# midicontrol_v6.net
KiCad netlist of a schematic drawn in EAGLE
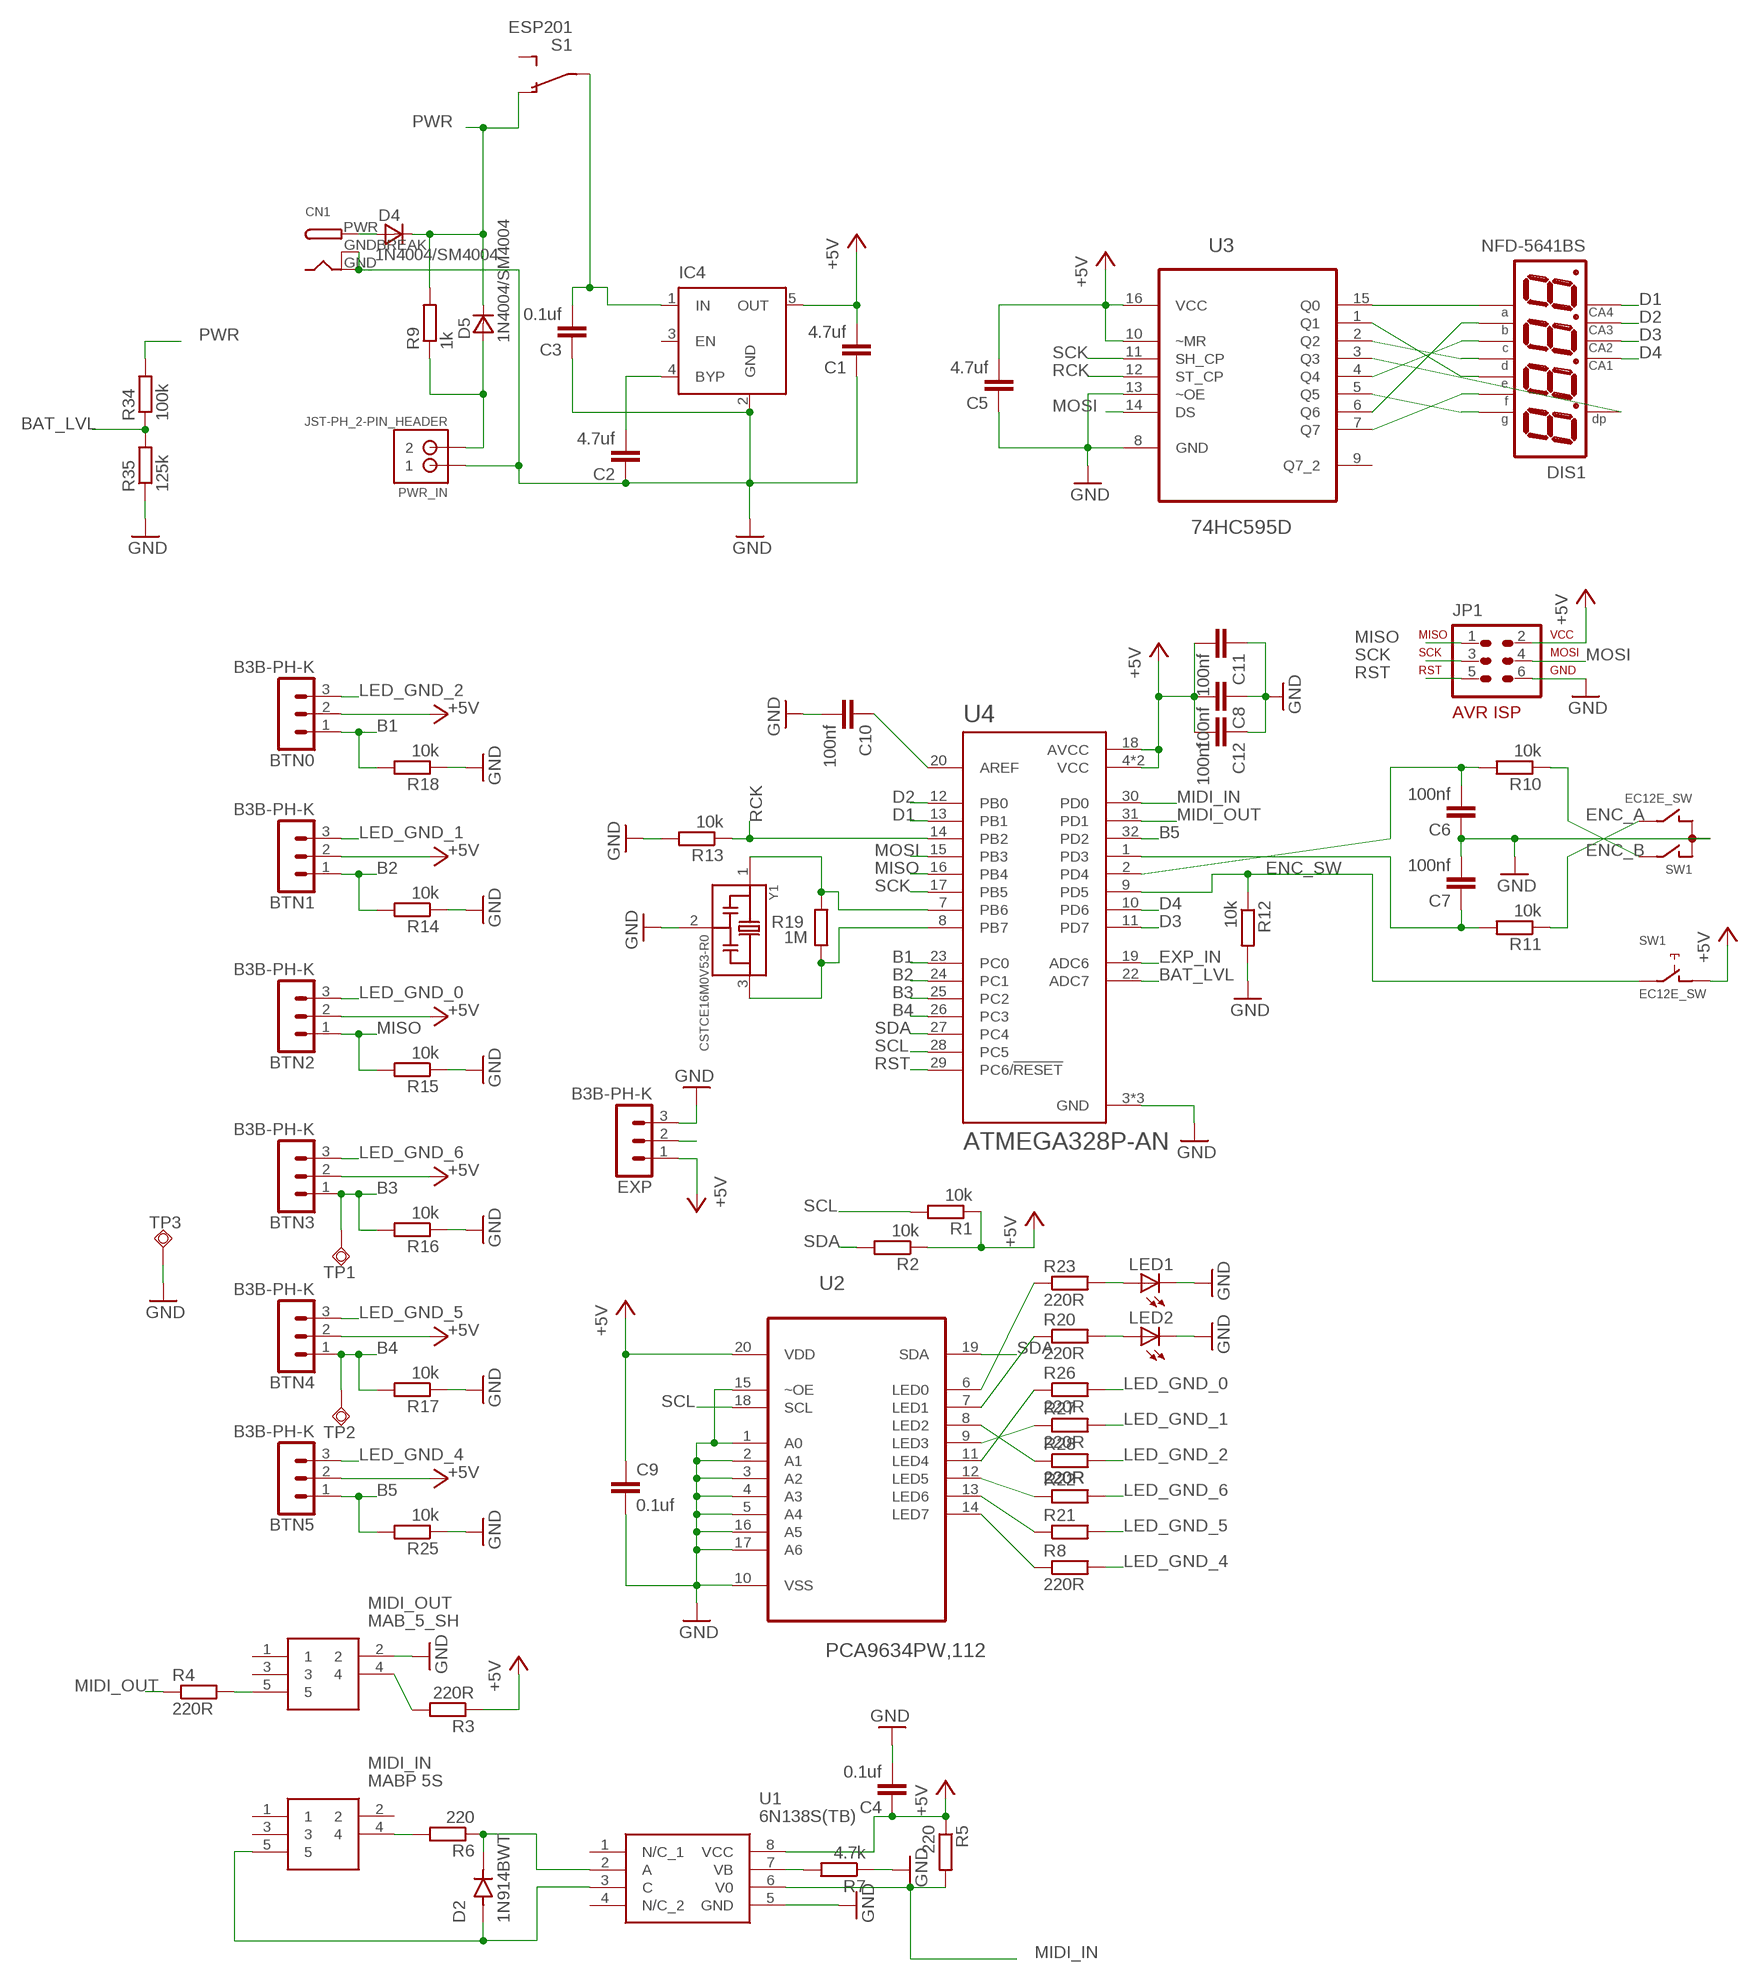
[diagram p0: schematic, sheet 1]

(export (version "E")
  (design (tool "Eeschema 10.0.6"))
  (components
    (comp (ref "BTN0")
      (value "B3B-PH-K")
      (footprint "eagle-import:B3B-PH-K")
      (libsource (lib "eagle-import") (part "B3B-PH-K"))
    )
    (comp (ref "BTN1")
      (value "B3B-PH-K")
      (footprint "eagle-import:B3B-PH-K")
      (libsource (lib "eagle-import") (part "B3B-PH-K"))
    )
    (comp (ref "BTN2")
      (value "B3B-PH-K")
      (footprint "eagle-import:B3B-PH-K")
      (libsource (lib "eagle-import") (part "B3B-PH-K"))
    )
    (comp (ref "BTN3")
      (value "B3B-PH-K")
      (footprint "eagle-import:B3B-PH-K")
      (libsource (lib "eagle-import") (part "B3B-PH-K"))
    )
    (comp (ref "BTN4")
      (value "B3B-PH-K")
      (footprint "eagle-import:B3B-PH-K")
      (libsource (lib "eagle-import") (part "B3B-PH-K"))
    )
    (comp (ref "BTN5")
      (value "B3B-PH-K")
      (footprint "eagle-import:B3B-PH-K")
      (libsource (lib "eagle-import") (part "B3B-PH-K"))
    )
    (comp (ref "C1")
      (value "4.7uf")
      (footprint "eagle-import:C1206")
      (libsource (lib "eagle-import") (part "C-EUC1206"))
    )
    (comp (ref "C2")
      (value "4.7uf")
      (footprint "eagle-import:C1206")
      (libsource (lib "eagle-import") (part "C-EUC1206"))
    )
    (comp (ref "C3")
      (value "0.1uf")
      (footprint "eagle-import:C0603")
      (libsource (lib "eagle-import") (part "C-EUC0603"))
    )
    (comp (ref "C4")
      (value "0.1uf")
      (footprint "eagle-import:C0603")
      (libsource (lib "eagle-import") (part "C-EUC0603"))
    )
    (comp (ref "C5")
      (value "4.7uf")
      (footprint "eagle-import:C0603")
      (libsource (lib "eagle-import") (part "C-EUC0603"))
    )
    (comp (ref "C6")
      (value "100nf")
      (footprint "eagle-import:C0603")
      (libsource (lib "eagle-import") (part "C-EUC0603"))
    )
    (comp (ref "C7")
      (value "100nf")
      (footprint "eagle-import:C0603")
      (libsource (lib "eagle-import") (part "C-EUC0603"))
    )
    (comp (ref "C8")
      (value "100nf")
      (footprint "eagle-import:C1206")
      (libsource (lib "eagle-import") (part "C-EUC1206"))
    )
    (comp (ref "C9")
      (value "0.1uf")
      (footprint "eagle-import:C0603")
      (libsource (lib "eagle-import") (part "C-EUC0603"))
    )
    (comp (ref "C10")
      (value "100nf")
      (footprint "eagle-import:C0603")
      (libsource (lib "eagle-import") (part "C-EUC0603"))
    )
    (comp (ref "C11")
      (value "100nf")
      (footprint "eagle-import:C0603")
      (libsource (lib "eagle-import") (part "C-EUC0603"))
    )
    (comp (ref "C12")
      (value "100nf")
      (footprint "eagle-import:C0603")
      (libsource (lib "eagle-import") (part "C-EUC0603"))
    )
    (comp (ref "CN1")
      (value "DCBARRELPTH")
      (footprint "eagle-import:DCJACK_2MM_PTH")
      (libsource (lib "eagle-import") (part "DCBARRELPTH"))
    )
    (comp (ref "D2")
      (value "1N914BWT")
      (footprint "eagle-import:SODFL1608X70N")
      (fields (field (name "MF") "ON Semiconductor"))
      (libsource (lib "eagle-import") (part "1N914BWT"))
    )
    (comp (ref "D4")
      (value "1N4004/SM4004")
      (footprint "eagle-import:MELF-MLL41")
      (libsource (lib "eagle-import") (part "SM4004"))
    )
    (comp (ref "D5")
      (value "1N4004/SM4004")
      (footprint "eagle-import:MELF-MLL41")
      (libsource (lib "eagle-import") (part "SM4004"))
    )
    (comp (ref "DIS1")
      (value "NFD-5641BS")
      (footprint "eagle-import:NFD-5641")
      (libsource (lib "eagle-import") (part "NFD-5641BS"))
    )
    (comp (ref "EXP")
      (value "B3B-PH-K")
      (footprint "eagle-import:B3B-PH-K")
      (libsource (lib "eagle-import") (part "B3B-PH-K"))
    )
    (comp (ref "IC4")
      (value "MIC5219XX")
      (footprint "eagle-import:SOT23-5")
      (libsource (lib "eagle-import") (part "MIC5219XX"))
    )
    (comp (ref "JP1")
      (value "AVR-ISP-6HORZ")
      (footprint "eagle-import:AVR-ISP-6R")
      (libsource (lib "eagle-import") (part "AVR-ISP-6HORZ"))
    )
    (comp (ref "LED1")
      (value "LED3MM")
      (footprint "eagle-import:LED3MM")
      (libsource (lib "eagle-import") (part "LED3MM"))
    )
    (comp (ref "LED2")
      (value "LED3MM")
      (footprint "eagle-import:LED3MM")
      (libsource (lib "eagle-import") (part "LED3MM"))
    )
    (comp (ref "MIDI_IN")
      (value "MABP 5S")
      (footprint "eagle-import:MAB-5-SH")
      (fields (field (name "MANUFACTURER_PART_NUMBER") "MAB 5 SH"))
      (libsource (lib "eagle-import") (part "MAB_5_SH"))
    )
    (comp (ref "MIDI_OUT")
      (value "MAB_5_SH")
      (footprint "eagle-import:MAB-5-SH")
      (fields (field (name "MANUFACTURER_PART_NUMBER") "MAB 5 SH"))
      (libsource (lib "eagle-import") (part "MAB_5_SH"))
    )
    (comp (ref "PWR_IN")
      (value "JST-PH_2-PIN_HEADER")
      (footprint "eagle-import:JST_B2B-PH_HEADER")
      (libsource (lib "eagle-import") (part "JST-PH_2-PIN_HEADER"))
    )
    (comp (ref "R1")
      (value "10k")
      (footprint "eagle-import:R0603")
      (libsource (lib "eagle-import") (part "rcl_334_R-EU_R0603"))
    )
    (comp (ref "R2")
      (value "10k")
      (footprint "eagle-import:R0603")
      (libsource (lib "eagle-import") (part "rcl_334_R-EU_R0603"))
    )
    (comp (ref "R3")
      (value "220R")
      (footprint "eagle-import:R0603")
      (libsource (lib "eagle-import") (part "rcl_334_R-EU_R0603"))
    )
    (comp (ref "R4")
      (value "220R")
      (footprint "eagle-import:R0603")
      (libsource (lib "eagle-import") (part "rcl_334_R-EU_R0603"))
    )
    (comp (ref "R5")
      (value "220")
      (footprint "eagle-import:R0603")
      (libsource (lib "eagle-import") (part "rcl_334_R-EU_R0603"))
    )
    (comp (ref "R6")
      (value "220")
      (footprint "eagle-import:R0603")
      (libsource (lib "eagle-import") (part "rcl_334_R-EU_R0603"))
    )
    (comp (ref "R7")
      (value "4.7k")
      (footprint "eagle-import:R0603")
      (libsource (lib "eagle-import") (part "rcl_334_R-EU_R0603"))
    )
    (comp (ref "R8")
      (value "220R")
      (footprint "eagle-import:R0603")
      (libsource (lib "eagle-import") (part "rcl_334_R-EU_R0603"))
    )
    (comp (ref "R9")
      (value "1k")
      (footprint "eagle-import:R0603")
      (libsource (lib "eagle-import") (part "rcl_334_R-EU_R0603"))
    )
    (comp (ref "R10")
      (value "10k")
      (footprint "eagle-import:R0603")
      (libsource (lib "eagle-import") (part "rcl_334_R-EU_R0603"))
    )
    (comp (ref "R11")
      (value "10k")
      (footprint "eagle-import:R0603")
      (libsource (lib "eagle-import") (part "rcl_334_R-EU_R0603"))
    )
    (comp (ref "R12")
      (value "10k")
      (footprint "eagle-import:R0603")
      (libsource (lib "eagle-import") (part "rcl_334_R-EU_R0603"))
    )
    (comp (ref "R13")
      (value "10k")
      (footprint "eagle-import:R0603")
      (libsource (lib "eagle-import") (part "rcl_334_R-EU_R0603"))
    )
    (comp (ref "R14")
      (value "10k")
      (footprint "eagle-import:R0603")
      (libsource (lib "eagle-import") (part "rcl_334_R-EU_R0603"))
    )
    (comp (ref "R15")
      (value "10k")
      (footprint "eagle-import:R0603")
      (libsource (lib "eagle-import") (part "rcl_334_R-EU_R0603"))
    )
    (comp (ref "R16")
      (value "10k")
      (footprint "eagle-import:R0603")
      (libsource (lib "eagle-import") (part "rcl_334_R-EU_R0603"))
    )
    (comp (ref "R17")
      (value "10k")
      (footprint "eagle-import:R0603")
      (libsource (lib "eagle-import") (part "rcl_334_R-EU_R0603"))
    )
    (comp (ref "R18")
      (value "10k")
      (footprint "eagle-import:R0603")
      (libsource (lib "eagle-import") (part "rcl_334_R-EU_R0603"))
    )
    (comp (ref "R19")
      (value "1M")
      (footprint "eagle-import:R0603-ROUND")
      (libsource (lib "eagle-import") (part "R-EU_R0603"))
    )
    (comp (ref "R20")
      (value "220R")
      (footprint "eagle-import:R0603")
      (libsource (lib "eagle-import") (part "rcl_334_R-EU_R0603"))
    )
    (comp (ref "R21")
      (value "220R")
      (footprint "eagle-import:R0603")
      (libsource (lib "eagle-import") (part "rcl_334_R-EU_R0603"))
    )
    (comp (ref "R22")
      (value "220R")
      (footprint "eagle-import:R0603")
      (libsource (lib "eagle-import") (part "rcl_334_R-EU_R0603"))
    )
    (comp (ref "R23")
      (value "220R")
      (footprint "eagle-import:R0603")
      (libsource (lib "eagle-import") (part "rcl_334_R-EU_R0603"))
    )
    (comp (ref "R25")
      (value "10k")
      (footprint "eagle-import:R0603")
      (libsource (lib "eagle-import") (part "rcl_334_R-EU_R0603"))
    )
    (comp (ref "R26")
      (value "220R")
      (footprint "eagle-import:R0603")
      (libsource (lib "eagle-import") (part "rcl_334_R-EU_R0603"))
    )
    (comp (ref "R27")
      (value "220R")
      (footprint "eagle-import:R0603")
      (libsource (lib "eagle-import") (part "rcl_334_R-EU_R0603"))
    )
    (comp (ref "R28")
      (value "220R")
      (footprint "eagle-import:R0603")
      (libsource (lib "eagle-import") (part "rcl_334_R-EU_R0603"))
    )
    (comp (ref "R34")
      (value "100k")
      (footprint "eagle-import:R0603")
      (libsource (lib "eagle-import") (part "rcl_334_R-EU_R0603"))
    )
    (comp (ref "R35")
      (value "125k")
      (footprint "eagle-import:R0603")
      (libsource (lib "eagle-import") (part "rcl_334_R-EU_R0603"))
    )
    (comp (ref "S1")
      (value "ESP201")
      (footprint "eagle-import:ESP201")
      (libsource (lib "eagle-import") (part "ESP201"))
    )
    (comp (ref "SW1")
      (value "EC12E_SW")
      (footprint "eagle-import:ALPS_EC12E_SW")
      (fields (field (name "MPN") "EC12E2424407"))
      (libsource (lib "eagle-import") (part "EC12E_SW"))
    )
    (comp (ref "TP1")
      (value "TPSQTP18R")
      (footprint "eagle-import:TP18R")
      (libsource (lib "eagle-import") (part "TPSQTP18R"))
    )
    (comp (ref "TP2")
      (value "TPSQTP18R")
      (footprint "eagle-import:TP18R")
      (libsource (lib "eagle-import") (part "TPSQTP18R"))
    )
    (comp (ref "TP3")
      (value "TPSQTP18R")
      (footprint "eagle-import:TP18R")
      (libsource (lib "eagle-import") (part "TPSQTP18R"))
    )
    (comp (ref "U1")
      (value "6N138S(TB)")
      (footprint "eagle-import:SOP254P1030X460-8N")
      (fields (field (name "MOUSER_PART_NUMBER") "638-6N138STB"))
      (libsource (lib "eagle-import") (part "6N138S(TB)"))
    )
    (comp (ref "U2")
      (value "PCA9634PW,112")
      (footprint "eagle-import:SOP65P640X110-20N")
      (fields (field (name "MF") "NXP USA"))
      (libsource (lib "eagle-import") (part "PCA9634PW,112"))
    )
    (comp (ref "U3")
      (value "74HC595D")
      (footprint "eagle-import:SOIC127P600X175-16N")
      (fields (field (name "MF") "Toshiba Semiconductor"))
      (libsource (lib "eagle-import") (part "74HC595D"))
    )
    (comp (ref "U4")
      (value "ATMEGA328P-AN")
      (footprint "eagle-import:QFP80P900X900X120-32N")
      (fields (field (name "MF") "Microchip"))
      (libsource (lib "eagle-import") (part "ATMEGA328P-AN"))
    )
    (comp (ref "Y1")
      (value "CSTCE16M0V53-R0")
      (footprint "eagle-import:OSC_CSTCE16M0V53-R0")
      (fields (field (name "MF") "Murata"))
      (libsource (lib "eagle-import") (part "CSTCE16M0V53-R0"))
    )
  )
  (nets
    (net (code "1") (name "+5V") (class "Default")
      (node (ref "BTN0") (pin "2") (pinfunction "2_2") (pintype "passive"))
      (node (ref "BTN1") (pin "2") (pinfunction "2_2") (pintype "passive"))
      (node (ref "BTN2") (pin "2") (pinfunction "2_2") (pintype "passive"))
      (node (ref "BTN3") (pin "2") (pinfunction "2_2") (pintype "passive"))
      (node (ref "BTN4") (pin "2") (pinfunction "2_2") (pintype "passive"))
      (node (ref "BTN5") (pin "2") (pinfunction "2_2") (pintype "passive"))
      (node (ref "C1") (pin "2") (pinfunction "2_2") (pintype "passive"))
      (node (ref "C11") (pin "2") (pinfunction "2_2") (pintype "passive"))
      (node (ref "C12") (pin "2") (pinfunction "2_2") (pintype "passive"))
      (node (ref "C4") (pin "1") (pinfunction "1_1") (pintype "passive"))
      (node (ref "C5") (pin "2") (pinfunction "2_2") (pintype "passive"))
      (node (ref "C8") (pin "2") (pinfunction "2_2") (pintype "passive"))
      (node (ref "C9") (pin "1") (pinfunction "1_1") (pintype "passive"))
      (node (ref "EXP") (pin "1") (pinfunction "1_1") (pintype "passive"))
      (node (ref "IC4") (pin "5") (pinfunction "OUT_5") (pintype "output"))
      (node (ref "JP1") (pin "2") (pinfunction "2_2") (pintype "passive"))
      (node (ref "R1") (pin "1") (pinfunction "1_1") (pintype "passive"))
      (node (ref "R2") (pin "1") (pinfunction "1_1") (pintype "passive"))
      (node (ref "R3") (pin "1") (pinfunction "1_1") (pintype "passive"))
      (node (ref "R5") (pin "1") (pinfunction "1_1") (pintype "passive"))
      (node (ref "SW1") (pin "D") (pinfunction "1_D") (pintype "passive"))
      (node (ref "U1") (pin "8") (pinfunction "VCC_8") (pintype "power_in"))
      (node (ref "U2") (pin "20") (pinfunction "VDD_20") (pintype "power_in"))
      (node (ref "U3") (pin "10") (pinfunction "~{MR}_10") (pintype "passive"))
      (node (ref "U3") (pin "16") (pinfunction "VCC_16") (pintype "power_in"))
      (node (ref "U4") (pin "18") (pinfunction "AVCC_18") (pintype "power_in"))
      (node (ref "U4") (pin "4") (pinfunction "VCC_4") (pintype "power_in"))
      (node (ref "U4") (pin "6") (pinfunction "VCC_6") (pintype "power_in"))
    )
    (net (code "2") (name "/B1") (class "Default")
      (node (ref "BTN0") (pin "1") (pinfunction "1_1") (pintype "passive"))
      (node (ref "R18") (pin "2") (pinfunction "2_2") (pintype "passive"))
      (node (ref "U4") (pin "23") (pinfunction "PC0_23") (pintype "bidirectional"))
    )
    (net (code "3") (name "/B2") (class "Default")
      (node (ref "BTN1") (pin "1") (pinfunction "1_1") (pintype "passive"))
      (node (ref "R14") (pin "2") (pinfunction "2_2") (pintype "passive"))
      (node (ref "U4") (pin "24") (pinfunction "PC1_24") (pintype "bidirectional"))
    )
    (net (code "4") (name "/B3") (class "Default")
      (node (ref "BTN3") (pin "1") (pinfunction "1_1") (pintype "passive"))
      (node (ref "R16") (pin "2") (pinfunction "2_2") (pintype "passive"))
      (node (ref "TP1") (pin "TP") (pinfunction "TP_TP") (pintype "input"))
      (node (ref "U4") (pin "25") (pinfunction "PC2_25") (pintype "bidirectional"))
    )
    (net (code "5") (name "/B4") (class "Default")
      (node (ref "BTN4") (pin "1") (pinfunction "1_1") (pintype "passive"))
      (node (ref "R17") (pin "2") (pinfunction "2_2") (pintype "passive"))
      (node (ref "TP2") (pin "TP") (pinfunction "TP_TP") (pintype "input"))
      (node (ref "U4") (pin "26") (pinfunction "PC3_26") (pintype "bidirectional"))
    )
    (net (code "6") (name "/B5") (class "Default")
      (node (ref "BTN5") (pin "1") (pinfunction "1_1") (pintype "passive"))
      (node (ref "R25") (pin "2") (pinfunction "2_2") (pintype "passive"))
      (node (ref "U4") (pin "32") (pinfunction "PD2_32") (pintype "bidirectional"))
    )
    (net (code "7") (name "/BAT_LVL") (class "Default")
      (node (ref "R34") (pin "1") (pinfunction "1_1") (pintype "passive"))
      (node (ref "R35") (pin "2") (pinfunction "2_2") (pintype "passive"))
      (node (ref "U4") (pin "22") (pinfunction "ADC7_22") (pintype "bidirectional"))
    )
    (net (code "8") (name "/D1") (class "Default")
      (node (ref "DIS1") (pin "P$6") (pinfunction "P$6_P$6") (pintype "bidirectional"))
      (node (ref "U4") (pin "13") (pinfunction "PB1_13") (pintype "bidirectional"))
    )
    (net (code "9") (name "/D2") (class "Default")
      (node (ref "DIS1") (pin "P$8") (pinfunction "P$8_P$8") (pintype "bidirectional"))
      (node (ref "U4") (pin "12") (pinfunction "PB0_12") (pintype "bidirectional"))
    )
    (net (code "10") (name "/D3") (class "Default")
      (node (ref "DIS1") (pin "P$9") (pinfunction "P$9_P$9") (pintype "bidirectional"))
      (node (ref "U4") (pin "11") (pinfunction "PD7_11") (pintype "bidirectional"))
    )
    (net (code "11") (name "/D4") (class "Default")
      (node (ref "DIS1") (pin "P$12") (pinfunction "P$12_P$12") (pintype "bidirectional"))
      (node (ref "U4") (pin "10") (pinfunction "PD6_10") (pintype "bidirectional"))
    )
    (net (code "12") (name "/ENC_A") (class "Default")
      (node (ref "R10") (pin "1") (pinfunction "1_1") (pintype "passive"))
      (node (ref "SW1") (pin "A") (pinfunction "A_A") (pintype "passive"))
    )
    (net (code "13") (name "/ENC_B") (class "Default")
      (node (ref "R11") (pin "1") (pinfunction "1_1") (pintype "passive"))
      (node (ref "SW1") (pin "B") (pinfunction "B_B") (pintype "passive"))
    )
    (net (code "14") (name "/ENC_SW") (class "Default")
      (node (ref "R12") (pin "1") (pinfunction "1_1") (pintype "passive"))
      (node (ref "SW1") (pin "E") (pinfunction "2_E") (pintype "passive"))
      (node (ref "U4") (pin "9") (pinfunction "PD5_9") (pintype "bidirectional"))
    )
    (net (code "15") (name "/EXP_IN") (class "Default")
      (node (ref "EXP") (pin "2") (pinfunction "2_2") (pintype "passive"))
      (node (ref "U4") (pin "19") (pinfunction "ADC6_19") (pintype "bidirectional"))
    )
    (net (code "16") (name "/LED_GND_0") (class "Default")
      (node (ref "BTN2") (pin "3") (pinfunction "3_3") (pintype "passive"))
      (node (ref "R26") (pin "2") (pinfunction "2_2") (pintype "passive"))
    )
    (net (code "17") (name "/LED_GND_1") (class "Default")
      (node (ref "BTN1") (pin "3") (pinfunction "3_3") (pintype "passive"))
      (node (ref "R27") (pin "2") (pinfunction "2_2") (pintype "passive"))
    )
    (net (code "18") (name "/LED_GND_2") (class "Default")
      (node (ref "BTN0") (pin "3") (pinfunction "3_3") (pintype "passive"))
      (node (ref "R28") (pin "2") (pinfunction "2_2") (pintype "passive"))
    )
    (net (code "19") (name "/LED_GND_4") (class "Default")
      (node (ref "BTN5") (pin "3") (pinfunction "3_3") (pintype "passive"))
      (node (ref "R8") (pin "2") (pinfunction "2_2") (pintype "passive"))
    )
    (net (code "20") (name "/LED_GND_5") (class "Default")
      (node (ref "BTN4") (pin "3") (pinfunction "3_3") (pintype "passive"))
      (node (ref "R21") (pin "2") (pinfunction "2_2") (pintype "passive"))
    )
    (net (code "21") (name "/LED_GND_6") (class "Default")
      (node (ref "BTN3") (pin "3") (pinfunction "3_3") (pintype "passive"))
      (node (ref "R22") (pin "2") (pinfunction "2_2") (pintype "passive"))
    )
    (net (code "22") (name "/MIDI_IN") (class "Default")
      (node (ref "R5") (pin "2") (pinfunction "2_2") (pintype "passive"))
      (node (ref "U1") (pin "6") (pinfunction "V0_6") (pintype "bidirectional"))
      (node (ref "U4") (pin "30") (pinfunction "PD0_30") (pintype "bidirectional"))
    )
    (net (code "23") (name "/MIDI_OUT") (class "Default")
      (node (ref "R4") (pin "1") (pinfunction "1_1") (pintype "passive"))
      (node (ref "U4") (pin "31") (pinfunction "PD1_31") (pintype "bidirectional"))
    )
    (net (code "24") (name "/MISO") (class "Default")
      (node (ref "BTN2") (pin "1") (pinfunction "1_1") (pintype "passive"))
      (node (ref "JP1") (pin "1") (pinfunction "1_1") (pintype "passive"))
      (node (ref "R15") (pin "2") (pinfunction "2_2") (pintype "passive"))
      (node (ref "U4") (pin "16") (pinfunction "PB4_16") (pintype "bidirectional"))
    )
    (net (code "25") (name "/MOSI") (class "Default")
      (node (ref "JP1") (pin "4") (pinfunction "4_4") (pintype "passive"))
      (node (ref "U3") (pin "14") (pinfunction "DS_14") (pintype "input"))
      (node (ref "U4") (pin "15") (pinfunction "PB3_15") (pintype "bidirectional"))
    )
    (net (code "26") (name "/PWR") (class "Default")
      (node (ref "D4") (pin "C") (pinfunction "C_C") (pintype "passive"))
      (node (ref "D5") (pin "C") (pinfunction "C_C") (pintype "passive"))
      (node (ref "R34") (pin "2") (pinfunction "2_2") (pintype "passive"))
      (node (ref "R9") (pin "2") (pinfunction "2_2") (pintype "passive"))
      (node (ref "S1") (pin "P$3") (pinfunction "O_P$3") (pintype "passive"))
    )
    (net (code "27") (name "/RCK") (class "Default")
      (node (ref "R13") (pin "1") (pinfunction "1_1") (pintype "passive"))
      (node (ref "U3") (pin "12") (pinfunction "ST_CP_12") (pintype "passive"))
      (node (ref "U4") (pin "14") (pinfunction "PB2_14") (pintype "bidirectional"))
    )
    (net (code "28") (name "/RST") (class "Default")
      (node (ref "JP1") (pin "5") (pinfunction "5_5") (pintype "passive"))
      (node (ref "U4") (pin "29") (pinfunction "PC6/~{RESET}_29") (pintype "bidirectional"))
    )
    (net (code "29") (name "/SCK") (class "Default")
      (node (ref "JP1") (pin "3") (pinfunction "3_3") (pintype "passive"))
      (node (ref "U3") (pin "11") (pinfunction "SH_CP_11") (pintype "passive"))
      (node (ref "U4") (pin "17") (pinfunction "PB5_17") (pintype "bidirectional"))
    )
    (net (code "30") (name "/SCL") (class "Default")
      (node (ref "R1") (pin "2") (pinfunction "2_2") (pintype "passive"))
      (node (ref "U2") (pin "18") (pinfunction "SCL_18") (pintype "input"))
      (node (ref "U4") (pin "28") (pinfunction "PC5_28") (pintype "bidirectional"))
    )
    (net (code "31") (name "/SDA") (class "Default")
      (node (ref "R2") (pin "2") (pinfunction "2_2") (pintype "passive"))
      (node (ref "U2") (pin "19") (pinfunction "SDA_19") (pintype "bidirectional"))
      (node (ref "U4") (pin "27") (pinfunction "PC4_27") (pintype "bidirectional"))
    )
    (net (code "32") (name "GND") (class "Default")
      (node (ref "C1") (pin "1") (pinfunction "1_1") (pintype "passive"))
      (node (ref "C10") (pin "2") (pinfunction "2_2") (pintype "passive"))
      (node (ref "C11") (pin "1") (pinfunction "1_1") (pintype "passive"))
      (node (ref "C12") (pin "1") (pinfunction "1_1") (pintype "passive"))
      (node (ref "C2") (pin "1") (pinfunction "1_1") (pintype "passive"))
      (node (ref "C3") (pin "1") (pinfunction "1_1") (pintype "passive"))
      (node (ref "C4") (pin "2") (pinfunction "2_2") (pintype "passive"))
      (node (ref "C5") (pin "1") (pinfunction "1_1") (pintype "passive"))
      (node (ref "C6") (pin "1") (pinfunction "1_1") (pintype "passive"))
      (node (ref "C7") (pin "2") (pinfunction "2_2") (pintype "passive"))
      (node (ref "C8") (pin "1") (pinfunction "1_1") (pintype "passive"))
      (node (ref "C9") (pin "2") (pinfunction "2_2") (pintype "passive"))
      (node (ref "CN1") (pin "GND") (pinfunction "GND_GND") (pintype "power_in"))
      (node (ref "CN1") (pin "GNDBREAK") (pinfunction "GNDBREAK_GNDBREAK") (pintype "power_in"))
      (node (ref "EXP") (pin "3") (pinfunction "3_3") (pintype "passive"))
      (node (ref "IC4") (pin "2") (pinfunction "GND_2") (pintype "power_in"))
      (node (ref "JP1") (pin "6") (pinfunction "6_6") (pintype "passive"))
      (node (ref "LED1") (pin "K") (pinfunction "C_K") (pintype "passive"))
      (node (ref "LED2") (pin "K") (pinfunction "C_K") (pintype "passive"))
      (node (ref "MIDI_OUT") (pin "2") (pinfunction "2_2") (pintype "bidirectional"))
      (node (ref "PWR_IN") (pin "P1") (pinfunction "1_P1") (pintype "bidirectional"))
      (node (ref "R12") (pin "2") (pinfunction "2_2") (pintype "passive"))
      (node (ref "R13") (pin "2") (pinfunction "2_2") (pintype "passive"))
      (node (ref "R14") (pin "1") (pinfunction "1_1") (pintype "passive"))
      (node (ref "R15") (pin "1") (pinfunction "1_1") (pintype "passive"))
      (node (ref "R16") (pin "1") (pinfunction "1_1") (pintype "passive"))
      (node (ref "R17") (pin "1") (pinfunction "1_1") (pintype "passive"))
      (node (ref "R18") (pin "1") (pinfunction "1_1") (pintype "passive"))
      (node (ref "R25") (pin "1") (pinfunction "1_1") (pintype "passive"))
      (node (ref "R35") (pin "1") (pinfunction "1_1") (pintype "passive"))
      (node (ref "R7") (pin "1") (pinfunction "1_1") (pintype "passive"))
      (node (ref "SW1") (pin "C") (pinfunction "C_C") (pintype "passive"))
      (node (ref "TP3") (pin "TP") (pinfunction "TP_TP") (pintype "input"))
      (node (ref "U1") (pin "5") (pinfunction "GND_5") (pintype "power_in"))
      (node (ref "U2") (pin "1") (pinfunction "A0_1") (pintype "input"))
      (node (ref "U2") (pin "10") (pinfunction "VSS_10") (pintype "power_in"))
      (node (ref "U2") (pin "15") (pinfunction "~{OE}_15") (pintype "input"))
      (node (ref "U2") (pin "16") (pinfunction "A5_16") (pintype "input"))
      (node (ref "U2") (pin "17") (pinfunction "A6_17") (pintype "input"))
      (node (ref "U2") (pin "2") (pinfunction "A1_2") (pintype "input"))
      (node (ref "U2") (pin "3") (pinfunction "A2_3") (pintype "input"))
      (node (ref "U2") (pin "4") (pinfunction "A3_4") (pintype "input"))
      (node (ref "U2") (pin "5") (pinfunction "A4_5") (pintype "input"))
      (node (ref "U3") (pin "13") (pinfunction "~{OE}_13") (pintype "input"))
      (node (ref "U3") (pin "8") (pinfunction "GND_8") (pintype "passive"))
      (node (ref "U4") (pin "21") (pinfunction "GND_21") (pintype "power_in"))
      (node (ref "U4") (pin "3") (pinfunction "GND_3") (pintype "power_in"))
      (node (ref "U4") (pin "5") (pinfunction "GND_5") (pintype "power_in"))
      (node (ref "Y1") (pin "2") (pinfunction "2_2") (pintype "power_in"))
    )
    (net (code "33") (name "Net-(CN1-PadPWR)") (class "Default")
      (node (ref "CN1") (pin "PWR") (pinfunction "PWR_PWR") (pintype "power_in"))
      (node (ref "D4") (pin "A") (pinfunction "A_A") (pintype "passive"))
    )
    (net (code "34") (name "Net-(D2-K)") (class "Default")
      (node (ref "D2") (pin "C") (pinfunction "K_C") (pintype "passive"))
      (node (ref "R6") (pin "1") (pinfunction "1_1") (pintype "passive"))
      (node (ref "U1") (pin "2") (pinfunction "A_2") (pintype "bidirectional"))
    )
    (net (code "35") (name "Net-(IC4-BYP)") (class "Default")
      (node (ref "C2") (pin "2") (pinfunction "2_2") (pintype "passive"))
      (node (ref "IC4") (pin "4") (pinfunction "BYP_4") (pintype "passive"))
    )
    (net (code "36") (name "Net-(IC4-IN)") (class "Default")
      (node (ref "C3") (pin "2") (pinfunction "2_2") (pintype "passive"))
      (node (ref "IC4") (pin "1") (pinfunction "IN_1") (pintype "input"))
      (node (ref "S1") (pin "P$1") (pinfunction "P_P$1") (pintype "passive"))
    )
    (net (code "37") (name "Net-(LED1-PadA)") (class "Default")
      (node (ref "LED1") (pin "A") (pinfunction "A_A") (pintype "passive"))
      (node (ref "R23") (pin "2") (pinfunction "2_2") (pintype "passive"))
    )
    (net (code "38") (name "Net-(LED2-PadA)") (class "Default")
      (node (ref "LED2") (pin "A") (pinfunction "A_A") (pintype "passive"))
      (node (ref "R20") (pin "2") (pinfunction "2_2") (pintype "passive"))
    )
    (net (code "39") (name "Net-(MIDI_IN-Pad4)") (class "Default")
      (node (ref "MIDI_IN") (pin "4") (pinfunction "4_4") (pintype "bidirectional"))
      (node (ref "R6") (pin "2") (pinfunction "2_2") (pintype "passive"))
    )
    (net (code "40") (name "Net-(MIDI_OUT-Pad4)") (class "Default")
      (node (ref "MIDI_OUT") (pin "4") (pinfunction "4_4") (pintype "bidirectional"))
      (node (ref "R3") (pin "2") (pinfunction "2_2") (pintype "passive"))
    )
    (net (code "41") (name "Net-(MIDI_OUT-Pad5)") (class "Default")
      (node (ref "MIDI_OUT") (pin "5") (pinfunction "5_5") (pintype "bidirectional"))
      (node (ref "R4") (pin "2") (pinfunction "2_2") (pintype "passive"))
    )
    (net (code "42") (name "Net-(PWR_IN-2)") (class "Default")
      (node (ref "D5") (pin "A") (pinfunction "A_A") (pintype "passive"))
      (node (ref "PWR_IN") (pin "P2") (pinfunction "2_P2") (pintype "bidirectional"))
      (node (ref "R9") (pin "1") (pinfunction "1_1") (pintype "passive"))
    )
    (net (code "43") (name "Net-(U1-C)") (class "Default")
      (node (ref "D2") (pin "A") (pinfunction "A_A") (pintype "passive"))
      (node (ref "MIDI_IN") (pin "5") (pinfunction "5_5") (pintype "bidirectional"))
      (node (ref "U1") (pin "3") (pinfunction "C_3") (pintype "bidirectional"))
    )
    (net (code "44") (name "Net-(U1-VB)") (class "Default")
      (node (ref "R7") (pin "2") (pinfunction "2_2") (pintype "passive"))
      (node (ref "U1") (pin "7") (pinfunction "VB_7") (pintype "bidirectional"))
    )
    (net (code "45") (name "Net-(U2-LED0)") (class "Default")
      (node (ref "R23") (pin "1") (pinfunction "1_1") (pintype "passive"))
      (node (ref "U2") (pin "6") (pinfunction "LED0_6") (pintype "output"))
    )
    (net (code "46") (name "Net-(U2-LED1)") (class "Default")
      (node (ref "R20") (pin "1") (pinfunction "1_1") (pintype "passive"))
      (node (ref "U2") (pin "7") (pinfunction "LED1_7") (pintype "output"))
    )
    (net (code "47") (name "Net-(U2-LED2)") (class "Default")
      (node (ref "R28") (pin "1") (pinfunction "1_1") (pintype "passive"))
      (node (ref "U2") (pin "8") (pinfunction "LED2_8") (pintype "output"))
    )
    (net (code "48") (name "Net-(U2-LED3)") (class "Default")
      (node (ref "R27") (pin "1") (pinfunction "1_1") (pintype "passive"))
      (node (ref "U2") (pin "9") (pinfunction "LED3_9") (pintype "output"))
    )
    (net (code "49") (name "Net-(U2-LED4)") (class "Default")
      (node (ref "R26") (pin "1") (pinfunction "1_1") (pintype "passive"))
      (node (ref "U2") (pin "11") (pinfunction "LED4_11") (pintype "output"))
    )
    (net (code "50") (name "Net-(U2-LED5)") (class "Default")
      (node (ref "R22") (pin "1") (pinfunction "1_1") (pintype "passive"))
      (node (ref "U2") (pin "12") (pinfunction "LED5_12") (pintype "output"))
    )
    (net (code "51") (name "Net-(U2-LED6)") (class "Default")
      (node (ref "R21") (pin "1") (pinfunction "1_1") (pintype "passive"))
      (node (ref "U2") (pin "13") (pinfunction "LED6_13") (pintype "output"))
    )
    (net (code "52") (name "Net-(U2-LED7)") (class "Default")
      (node (ref "R8") (pin "1") (pinfunction "1_1") (pintype "passive"))
      (node (ref "U2") (pin "14") (pinfunction "LED7_14") (pintype "output"))
    )
    (net (code "53") (name "Net-(U3-Q0)") (class "Default")
      (node (ref "DIS1") (pin "P$11") (pinfunction "P$11_P$11") (pintype "bidirectional"))
      (node (ref "U3") (pin "15") (pinfunction "Q0_15") (pintype "output"))
    )
    (net (code "54") (name "Net-(U3-Q1)") (class "Default")
      (node (ref "DIS1") (pin "P$1") (pinfunction "P$1_P$1") (pintype "bidirectional"))
      (node (ref "U3") (pin "1") (pinfunction "Q1_1") (pintype "output"))
    )
    (net (code "55") (name "Net-(U3-Q2)") (class "Default")
      (node (ref "DIS1") (pin "P$2") (pinfunction "P$2_P$2") (pintype "bidirectional"))
      (node (ref "U3") (pin "2") (pinfunction "Q2_2") (pintype "output"))
    )
    (net (code "56") (name "Net-(U3-Q3)") (class "Default")
      (node (ref "DIS1") (pin "P$3") (pinfunction "P$3_P$3") (pintype "bidirectional"))
      (node (ref "U3") (pin "3") (pinfunction "Q3_3") (pintype "output"))
    )
    (net (code "57") (name "Net-(U3-Q4)") (class "Default")
      (node (ref "DIS1") (pin "P$4") (pinfunction "P$4_P$4") (pintype "bidirectional"))
      (node (ref "U3") (pin "4") (pinfunction "Q4_4") (pintype "output"))
    )
    (net (code "58") (name "Net-(U3-Q5)") (class "Default")
      (node (ref "DIS1") (pin "P$5") (pinfunction "P$5_P$5") (pintype "bidirectional"))
      (node (ref "U3") (pin "5") (pinfunction "Q5_5") (pintype "output"))
    )
    (net (code "59") (name "Net-(U3-Q6)") (class "Default")
      (node (ref "DIS1") (pin "P$7") (pinfunction "P$7_P$7") (pintype "bidirectional"))
      (node (ref "U3") (pin "6") (pinfunction "Q6_6") (pintype "output"))
    )
    (net (code "60") (name "Net-(U3-Q7)") (class "Default")
      (node (ref "DIS1") (pin "P$10") (pinfunction "P$10_P$10") (pintype "bidirectional"))
      (node (ref "U3") (pin "7") (pinfunction "Q7_7") (pintype "output"))
    )
    (net (code "61") (name "Net-(U4-AREF)") (class "Default")
      (node (ref "C10") (pin "1") (pinfunction "1_1") (pintype "passive"))
      (node (ref "U4") (pin "20") (pinfunction "AREF_20") (pintype "input"))
    )
    (net (code "62") (name "Net-(U4-PB6)") (class "Default")
      (node (ref "R19") (pin "2") (pinfunction "2_2") (pintype "passive"))
      (node (ref "U4") (pin "7") (pinfunction "PB6_7") (pintype "bidirectional"))
      (node (ref "Y1") (pin "1") (pinfunction "1_1") (pintype "passive"))
    )
    (net (code "63") (name "Net-(U4-PB7)") (class "Default")
      (node (ref "R19") (pin "1") (pinfunction "1_1") (pintype "passive"))
      (node (ref "U4") (pin "8") (pinfunction "PB7_8") (pintype "bidirectional"))
      (node (ref "Y1") (pin "3") (pinfunction "3_3") (pintype "passive"))
    )
    (net (code "64") (name "Net-(U4-PD3)") (class "Default")
      (node (ref "C7") (pin "1") (pinfunction "1_1") (pintype "passive"))
      (node (ref "R11") (pin "2") (pinfunction "2_2") (pintype "passive"))
      (node (ref "U4") (pin "1") (pinfunction "PD3_1") (pintype "bidirectional"))
    )
    (net (code "65") (name "Net-(U4-PD4)") (class "Default")
      (node (ref "C6") (pin "2") (pinfunction "2_2") (pintype "passive"))
      (node (ref "R10") (pin "2") (pinfunction "2_2") (pintype "passive"))
      (node (ref "U4") (pin "2") (pinfunction "PD4_2") (pintype "bidirectional"))
    )
    (net (code "66") (name "unconnected-(IC4-EN-Pad3)") (class "Default")
      (node (ref "IC4") (pin "3") (pinfunction "EN_3") (pintype "input"))
    )
    (net (code "67") (name "unconnected-(MIDI_IN-Pad1)") (class "Default")
      (node (ref "MIDI_IN") (pin "1") (pinfunction "1_1") (pintype "bidirectional"))
    )
    (net (code "68") (name "unconnected-(MIDI_IN-Pad2)") (class "Default")
      (node (ref "MIDI_IN") (pin "2") (pinfunction "2_2") (pintype "bidirectional"))
    )
    (net (code "69") (name "unconnected-(MIDI_IN-Pad3)") (class "Default")
      (node (ref "MIDI_IN") (pin "3") (pinfunction "3_3") (pintype "bidirectional"))
    )
    (net (code "70") (name "unconnected-(MIDI_OUT-Pad1)") (class "Default")
      (node (ref "MIDI_OUT") (pin "1") (pinfunction "1_1") (pintype "bidirectional"))
    )
    (net (code "71") (name "unconnected-(MIDI_OUT-Pad3)") (class "Default")
      (node (ref "MIDI_OUT") (pin "3") (pinfunction "3_3") (pintype "bidirectional"))
    )
    (net (code "72") (name "unconnected-(S1-S-PadP$2)") (class "Default")
      (node (ref "S1") (pin "P$2") (pinfunction "S_P$2") (pintype "passive"))
    )
    (net (code "73") (name "unconnected-(U1-N{slash}C_1-Pad1)") (class "Default")
      (node (ref "U1") (pin "1") (pinfunction "N/C_1_1") (pintype "bidirectional"))
    )
    (net (code "74") (name "unconnected-(U1-N{slash}C_2-Pad4)") (class "Default")
      (node (ref "U1") (pin "4") (pinfunction "N/C_2_4") (pintype "bidirectional"))
    )
    (net (code "75") (name "unconnected-(U3-Q7_2-Pad9)") (class "Default")
      (node (ref "U3") (pin "9") (pinfunction "Q7_2_9") (pintype "output"))
    )
  )
)
